# pripravek.net
KiCad netlist of a schematic drawn in EAGLE
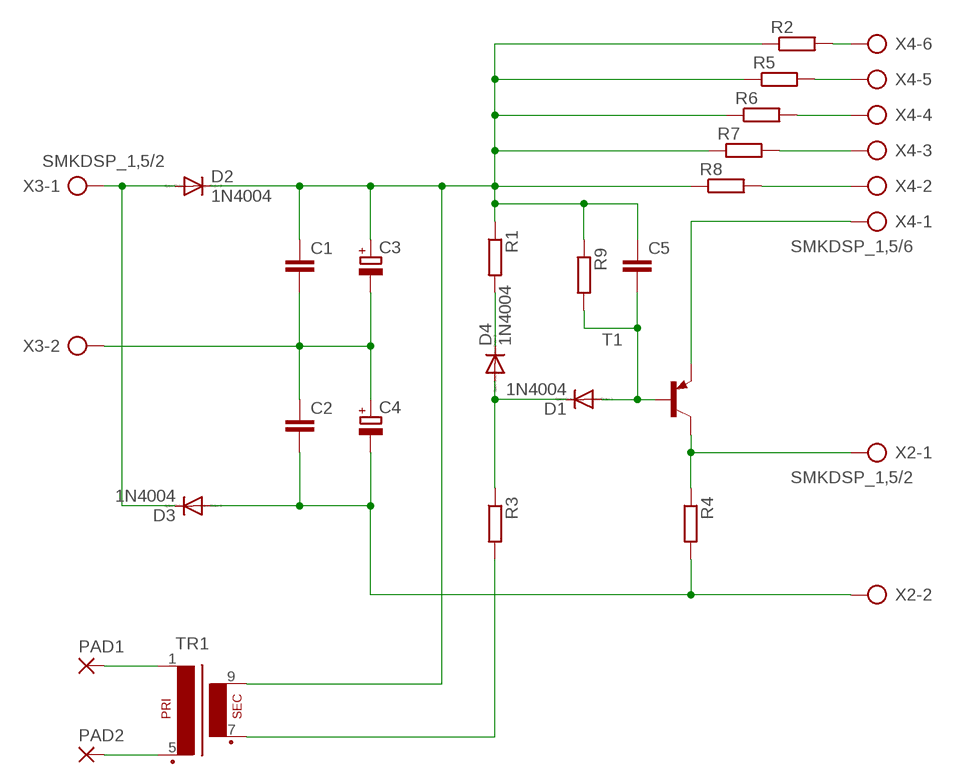
[diagram p0: schematic, sheet 1]

(export (version "E")
  (design (tool "Eeschema 10.0.6"))
  (components
    (comp (ref "C1")
      (value "C-EU050-035X075")
      (footprint "eagle-import:C050-035X075")
      (libsource (lib "eagle-import") (part "C-EU050-035X075"))
    )
    (comp (ref "C2")
      (value "C-EU050-035X075")
      (footprint "eagle-import:C050-035X075")
      (libsource (lib "eagle-import") (part "C-EU050-035X075"))
    )
    (comp (ref "C3")
      (value "CPOL-EUE5-8.5")
      (footprint "eagle-import:E5-8,5")
      (libsource (lib "eagle-import") (part "CPOL-EUE5-8.5"))
    )
    (comp (ref "C4")
      (value "CPOL-EUE5-8.5")
      (footprint "eagle-import:E5-8,5")
      (libsource (lib "eagle-import") (part "CPOL-EUE5-8.5"))
    )
    (comp (ref "C5")
      (value "C-EU050-035X075")
      (footprint "eagle-import:C050-035X075")
      (libsource (lib "eagle-import") (part "C-EU050-035X075"))
    )
    (comp (ref "D1")
      (value "1N4004")
      (footprint "eagle-import:DO41-10")
      (libsource (lib "eagle-import") (part "1N4004"))
    )
    (comp (ref "D2")
      (value "1N4004")
      (footprint "eagle-import:DO41-10")
      (libsource (lib "eagle-import") (part "1N4004"))
    )
    (comp (ref "D3")
      (value "1N4004")
      (footprint "eagle-import:DO41-10")
      (libsource (lib "eagle-import") (part "1N4004"))
    )
    (comp (ref "D4")
      (value "1N4004")
      (footprint "eagle-import:DO41-10")
      (libsource (lib "eagle-import") (part "1N4004"))
    )
    (comp (ref "PAD1")
      (value "3,81/1,3")
      (footprint "eagle-import:3,81_1,3")
      (libsource (lib "eagle-import") (part "3,81/1,3"))
    )
    (comp (ref "PAD2")
      (value "3,81/1,3")
      (footprint "eagle-import:3,81_1,3")
      (libsource (lib "eagle-import") (part "3,81/1,3"))
    )
    (comp (ref "R1")
      (value "R-EU_0207/12")
      (footprint "eagle-import:0207_12")
      (libsource (lib "eagle-import") (part "R-EU_0207/12"))
    )
    (comp (ref "R2")
      (value "R-EU_0411/15")
      (footprint "eagle-import:0411_15")
      (libsource (lib "eagle-import") (part "R-EU_0411/15"))
    )
    (comp (ref "R3")
      (value "R-EU_0207/12")
      (footprint "eagle-import:0207_12")
      (libsource (lib "eagle-import") (part "R-EU_0207/12"))
    )
    (comp (ref "R4")
      (value "R-EU_0207/12")
      (footprint "eagle-import:0207_12")
      (libsource (lib "eagle-import") (part "R-EU_0207/12"))
    )
    (comp (ref "R5")
      (value "R-EU_0411/15")
      (footprint "eagle-import:0411_15")
      (libsource (lib "eagle-import") (part "R-EU_0411/15"))
    )
    (comp (ref "R6")
      (value "R-EU_0411/15")
      (footprint "eagle-import:0411_15")
      (libsource (lib "eagle-import") (part "R-EU_0411/15"))
    )
    (comp (ref "R7")
      (value "R-EU_0411/15")
      (footprint "eagle-import:0411_15")
      (libsource (lib "eagle-import") (part "R-EU_0411/15"))
    )
    (comp (ref "R8")
      (value "R-EU_0411/15")
      (footprint "eagle-import:0411_15")
      (libsource (lib "eagle-import") (part "R-EU_0411/15"))
    )
    (comp (ref "R9")
      (value "R-EU_0207/12")
      (footprint "eagle-import:0207_12")
      (libsource (lib "eagle-import") (part "R-EU_0207/12"))
    )
    (comp (ref "T1")
      (value "-PNP-TO220V")
      (footprint "eagle-import:TO220V")
      (libsource (lib "eagle-import") (part "-PNP-TO220V"))
    )
    (comp (ref "TR1")
      (value "EI30-1")
      (footprint "eagle-import:EI30-1")
      (libsource (lib "eagle-import") (part "EI30-1"))
    )
    (comp (ref "X2")
      (value "SMKDSP_1,5/2")
      (footprint "eagle-import:SMKDSP_1,5_2")
      (fields (field (name "MF") "FARNELL") (field (name "MPN") "1733570"))
      (libsource (lib "eagle-import") (part "SMKDSP_1,5/2"))
    )
    (comp (ref "X3")
      (value "SMKDSP_1,5/2")
      (footprint "eagle-import:SMKDSP_1,5_2")
      (fields (field (name "MF") "FARNELL") (field (name "MPN") "1733570"))
      (libsource (lib "eagle-import") (part "SMKDSP_1,5/2"))
    )
    (comp (ref "X4")
      (value "SMKDSP_1,5/6")
      (footprint "eagle-import:SMKDSP_1,5_6")
      (fields (field (name "MF") "FARNELL") (field (name "MPN") "1733619"))
      (libsource (lib "eagle-import") (part "SMKDSP_1,5/6"))
    )
  )
  (nets
    (net (code "1") (name "Net-(D1-PadC)") (class "Default")
      (node (ref "D1") (pin "C") (pinfunction "C_C") (pintype "passive"))
      (node (ref "D4") (pin "A") (pinfunction "A_A") (pintype "passive"))
      (node (ref "R3") (pin "1") (pinfunction "1_1") (pintype "passive"))
    )
    (net (code "2") (name "Net-(D4-PadC)") (class "Default")
      (node (ref "D4") (pin "C") (pinfunction "C_C") (pintype "passive"))
      (node (ref "R1") (pin "2") (pinfunction "2_2") (pintype "passive"))
    )
    (net (code "3") (name "Net-(PAD1-P)") (class "Default")
      (node (ref "PAD1") (pin "1") (pinfunction "P_1") (pintype "passive"))
      (node (ref "TR1") (pin "1") (pinfunction "P1_1") (pintype "passive"))
    )
    (net (code "4") (name "Net-(PAD2-P)") (class "Default")
      (node (ref "PAD2") (pin "1") (pinfunction "P_1") (pintype "passive"))
      (node (ref "TR1") (pin "5") (pinfunction "P2_5") (pintype "passive"))
    )
    (net (code "5") (name "Net-(T1-B)") (class "Default")
      (node (ref "C5") (pin "2") (pinfunction "2_2") (pintype "passive"))
      (node (ref "D1") (pin "A") (pinfunction "A_A") (pintype "passive"))
      (node (ref "R9") (pin "2") (pinfunction "2_2") (pintype "passive"))
      (node (ref "T1") (pin "1") (pinfunction "B_1") (pintype "passive"))
    )
    (net (code "6") (name "Net-(T1-C)") (class "Default")
      (node (ref "R4") (pin "1") (pinfunction "1_1") (pintype "passive"))
      (node (ref "T1") (pin "2") (pinfunction "C_2") (pintype "passive"))
      (node (ref "X2") (pin "1") (pinfunction "KL_1") (pintype "passive"))
    )
    (net (code "7") (name "Net-(T1-E)") (class "Default")
      (node (ref "T1") (pin "3") (pinfunction "E_3") (pintype "passive"))
      (node (ref "X4") (pin "1") (pinfunction "KL_1") (pintype "passive"))
    )
    (net (code "8") (name "Net-(TR1-S3)") (class "Default")
      (node (ref "R3") (pin "2") (pinfunction "2_2") (pintype "passive"))
      (node (ref "TR1") (pin "7") (pinfunction "S3_7") (pintype "passive"))
    )
    (net (code "9") (name "Net-(TR1-S4)") (class "Default")
      (node (ref "C1") (pin "1") (pinfunction "1_1") (pintype "passive"))
      (node (ref "C3") (pin "+") (pinfunction "+_+") (pintype "passive"))
      (node (ref "C5") (pin "1") (pinfunction "1_1") (pintype "passive"))
      (node (ref "D2") (pin "C") (pinfunction "C_C") (pintype "passive"))
      (node (ref "R1") (pin "1") (pinfunction "1_1") (pintype "passive"))
      (node (ref "R2") (pin "1") (pinfunction "1_1") (pintype "passive"))
      (node (ref "R5") (pin "1") (pinfunction "1_1") (pintype "passive"))
      (node (ref "R6") (pin "1") (pinfunction "1_1") (pintype "passive"))
      (node (ref "R7") (pin "1") (pinfunction "1_1") (pintype "passive"))
      (node (ref "R8") (pin "1") (pinfunction "1_1") (pintype "passive"))
      (node (ref "R9") (pin "1") (pinfunction "1_1") (pintype "passive"))
      (node (ref "TR1") (pin "9") (pinfunction "S4_9") (pintype "passive"))
    )
    (net (code "10") (name "Net-(X2B-KL)") (class "Default")
      (node (ref "C2") (pin "2") (pinfunction "2_2") (pintype "passive"))
      (node (ref "C4") (pin "-") (pinfunction "-_-") (pintype "passive"))
      (node (ref "D3") (pin "A") (pinfunction "A_A") (pintype "passive"))
      (node (ref "R4") (pin "2") (pinfunction "2_2") (pintype "passive"))
      (node (ref "X2") (pin "2") (pinfunction "KL_2") (pintype "passive"))
    )
    (net (code "11") (name "Net-(X3A-KL)") (class "Default")
      (node (ref "D2") (pin "A") (pinfunction "A_A") (pintype "passive"))
      (node (ref "D3") (pin "C") (pinfunction "C_C") (pintype "passive"))
      (node (ref "X3") (pin "1") (pinfunction "KL_1") (pintype "passive"))
    )
    (net (code "12") (name "Net-(X3B-KL)") (class "Default")
      (node (ref "C1") (pin "2") (pinfunction "2_2") (pintype "passive"))
      (node (ref "C2") (pin "1") (pinfunction "1_1") (pintype "passive"))
      (node (ref "C3") (pin "-") (pinfunction "-_-") (pintype "passive"))
      (node (ref "C4") (pin "+") (pinfunction "+_+") (pintype "passive"))
      (node (ref "X3") (pin "2") (pinfunction "KL_2") (pintype "passive"))
    )
    (net (code "13") (name "Net-(X4B-KL)") (class "Default")
      (node (ref "R8") (pin "2") (pinfunction "2_2") (pintype "passive"))
      (node (ref "X4") (pin "2") (pinfunction "KL_2") (pintype "passive"))
    )
    (net (code "14") (name "Net-(X4C-KL)") (class "Default")
      (node (ref "R7") (pin "2") (pinfunction "2_2") (pintype "passive"))
      (node (ref "X4") (pin "3") (pinfunction "KL_3") (pintype "passive"))
    )
    (net (code "15") (name "Net-(X4D-KL)") (class "Default")
      (node (ref "R6") (pin "2") (pinfunction "2_2") (pintype "passive"))
      (node (ref "X4") (pin "4") (pinfunction "KL_4") (pintype "passive"))
    )
    (net (code "16") (name "Net-(X4E-KL)") (class "Default")
      (node (ref "R5") (pin "2") (pinfunction "2_2") (pintype "passive"))
      (node (ref "X4") (pin "5") (pinfunction "KL_5") (pintype "passive"))
    )
    (net (code "17") (name "Net-(X4F-KL)") (class "Default")
      (node (ref "R2") (pin "2") (pinfunction "2_2") (pintype "passive"))
      (node (ref "X4") (pin "6") (pinfunction "KL_6") (pintype "passive"))
    )
  )
)
